# LED_eyeSocket.net
KiCad netlist of a schematic drawn in EAGLE
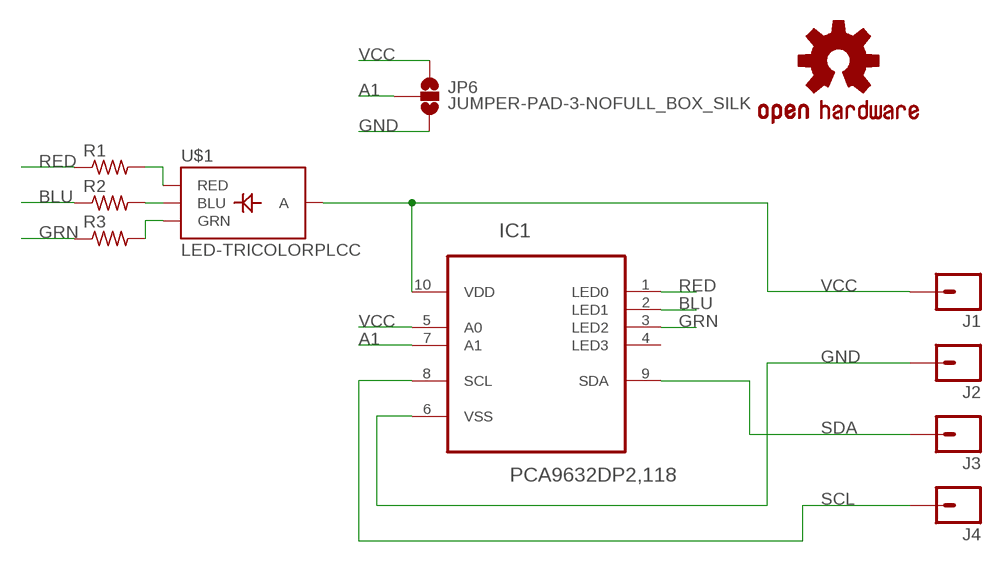
[diagram p0: schematic, sheet 1]

(export (version "E")
  (design (tool "Eeschema 10.0.6"))
  (components
    (comp (ref "IC1")
      (value "PCA9632DP2,118")
      (footprint "eagle-import:SOP50P490X110-10N")
      (libsource (lib "eagle-import") (part "PCA9632DP2,118"))
    )
    (comp (ref "J1")
      (value "M01NOSILK-KIT")
      (footprint "eagle-import:1X01NS-KIT")
      (libsource (lib "eagle-import") (part "M01NOSILK-KIT"))
    )
    (comp (ref "J2")
      (value "M01NOSILK-KIT")
      (footprint "eagle-import:1X01NS-KIT")
      (libsource (lib "eagle-import") (part "M01NOSILK-KIT"))
    )
    (comp (ref "J3")
      (value "M01NOSILK-KIT")
      (footprint "eagle-import:1X01NS-KIT")
      (libsource (lib "eagle-import") (part "M01NOSILK-KIT"))
    )
    (comp (ref "J4")
      (value "M01NOSILK-KIT")
      (footprint "eagle-import:1X01NS-KIT")
      (libsource (lib "eagle-import") (part "M01NOSILK-KIT"))
    )
    (comp (ref "JP6")
      (value "JUMPER-PAD-3-NOFULL_BOX_SILK")
      (footprint "eagle-import:PAD-JUMPER-3-NO_YES_SILK_FULL_BOX")
      (libsource (lib "eagle-import") (part "JUMPER-PAD-3-NOFULL_BOX_SILK"))
    )
    (comp (ref "LOGO1")
      (value "OSHW-LOGOS")
      (footprint "eagle-import:OSHW-LOGO-S")
      (libsource (lib "eagle-import") (part "OSHW-LOGOS"))
    )
    (comp (ref "R1")
      (value "R-US_R0603")
      (footprint "eagle-import:R0603")
      (libsource (lib "eagle-import") (part "R-US_R0603"))
    )
    (comp (ref "R2")
      (value "R-US_R0603")
      (footprint "eagle-import:R0603")
      (libsource (lib "eagle-import") (part "R-US_R0603"))
    )
    (comp (ref "R3")
      (value "R-US_R0603")
      (footprint "eagle-import:R0603")
      (libsource (lib "eagle-import") (part "R-US_R0603"))
    )
    (comp (ref "U$1")
      (value "LED-TRICOLORPLCC")
      (footprint "eagle-import:LED-TRICOLOR-PLCC")
      (libsource (lib "eagle-import") (part "LED-TRICOLORPLCC"))
    )
  )
  (nets
    (net (code "1") (name "/A1") (class "Default")
      (node (ref "IC1") (pin "7") (pinfunction "A1_7") (pintype "input"))
      (node (ref "JP6") (pin "2") (pinfunction "2_2") (pintype "passive"))
    )
    (net (code "2") (name "/BLU") (class "Default")
      (node (ref "IC1") (pin "2") (pinfunction "LED1_2") (pintype "output"))
      (node (ref "R2") (pin "1") (pinfunction "1_1") (pintype "passive"))
    )
    (net (code "3") (name "/GND") (class "Default")
      (node (ref "IC1") (pin "6") (pinfunction "VSS_6") (pintype "power_in"))
      (node (ref "J2") (pin "1") (pinfunction "1_1") (pintype "passive"))
      (node (ref "JP6") (pin "3") (pinfunction "3_3") (pintype "passive"))
    )
    (net (code "4") (name "/GRN") (class "Default")
      (node (ref "IC1") (pin "3") (pinfunction "LED2_3") (pintype "output"))
      (node (ref "R3") (pin "1") (pinfunction "1_1") (pintype "passive"))
    )
    (net (code "5") (name "/RED") (class "Default")
      (node (ref "IC1") (pin "1") (pinfunction "LED0_1") (pintype "output"))
      (node (ref "R1") (pin "1") (pinfunction "1_1") (pintype "passive"))
    )
    (net (code "6") (name "/SCL") (class "Default")
      (node (ref "IC1") (pin "8") (pinfunction "SCL_8") (pintype "input"))
      (node (ref "J4") (pin "1") (pinfunction "1_1") (pintype "passive"))
    )
    (net (code "7") (name "/SDA") (class "Default")
      (node (ref "IC1") (pin "9") (pinfunction "SDA_9") (pintype "bidirectional"))
      (node (ref "J3") (pin "1") (pinfunction "1_1") (pintype "passive"))
    )
    (net (code "8") (name "/VCC") (class "Default")
      (node (ref "IC1") (pin "10") (pinfunction "VDD_10") (pintype "power_in"))
      (node (ref "IC1") (pin "5") (pinfunction "A0_5") (pintype "input"))
      (node (ref "J1") (pin "1") (pinfunction "1_1") (pintype "passive"))
      (node (ref "JP6") (pin "1") (pinfunction "1_1") (pintype "passive"))
      (node (ref "U$1") (pin "PAD1") (pinfunction "A_PAD1") (pintype "bidirectional"))
    )
    (net (code "9") (name "Net-(U$1-BLU)") (class "Default")
      (node (ref "R2") (pin "2") (pinfunction "2_2") (pintype "passive"))
      (node (ref "U$1") (pin "PAD2") (pinfunction "BLU_PAD2") (pintype "bidirectional"))
    )
    (net (code "10") (name "Net-(U$1-GRN)") (class "Default")
      (node (ref "R3") (pin "2") (pinfunction "2_2") (pintype "passive"))
      (node (ref "U$1") (pin "PAD3") (pinfunction "GRN_PAD3") (pintype "bidirectional"))
    )
    (net (code "11") (name "Net-(U$1-RED)") (class "Default")
      (node (ref "R1") (pin "2") (pinfunction "2_2") (pintype "passive"))
      (node (ref "U$1") (pin "PAD4") (pinfunction "RED_PAD4") (pintype "bidirectional"))
    )
    (net (code "12") (name "unconnected-(IC1-LED3-Pad4)") (class "Default")
      (node (ref "IC1") (pin "4") (pinfunction "LED3_4") (pintype "output"))
    )
  )
)
